# GSM_Power_Source.net
KiCad netlist of a schematic drawn in Altium Designer
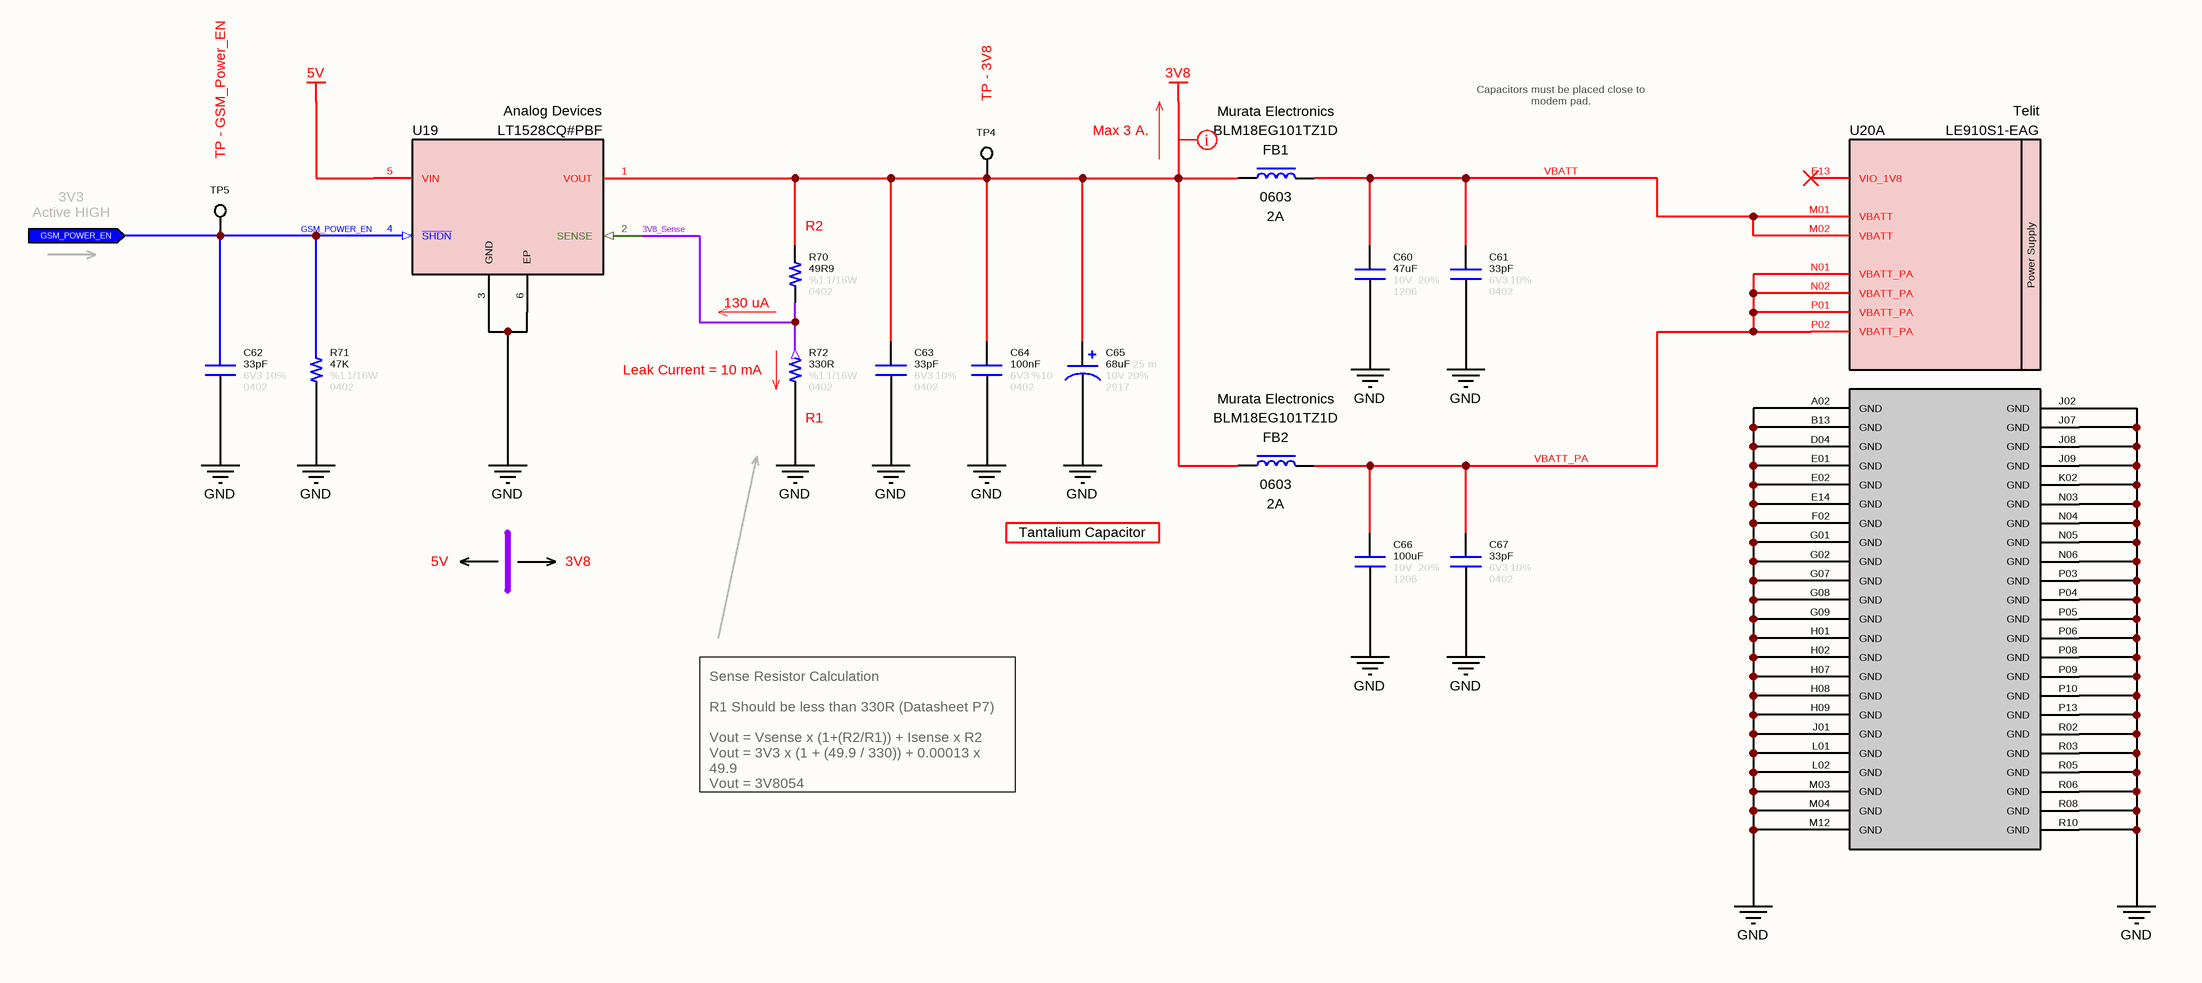
[diagram p0: GSM Power Source.SchDoc]

(export (version "E")
  (design (tool "Eeschema 10.0.6"))
  (components
    (comp (ref "C60")
      (value "47uF")
      (footprint "CAPACITOR_1206")
      (description "Multilayer Ceramic Capacitors MLCC - SMD/SMT 47UF 10V 20% 1206")
      (fields
        (field (name "MANUFACTURER PART NUMBER") "C1206C476M8PAC")
        (field (name "TOLERANCE") "20%")
        (field (name "CASE") "1206")
        (field (name "VOLTAGE") "10V")
        (field (name "Comment") "Capacitor - 47uF [1206] (Ceramic)")
      )
      (libsource (lib "Akkoyun") (part "Capacitor - 47uF [1206-10V]"))
    )
    (comp (ref "C61")
      (value "33pF")
      (footprint "CAPACITOR_0402")
      (description "Capacitor - 33pF [0402] (Ceramic)")
      (fields
        (field (name "MANUFACTURER PART NUMBER") "C0402C330J9RACAUTO")
        (field (name "TOLERANCE") "10%")
        (field (name "CASE") "0402")
        (field (name "VOLTAGE") "6V3")
      )
      (libsource (lib "Akkoyun") (part "Capacitor - 33pF [0402-6V3]"))
    )
    (comp (ref "C62")
      (value "33pF")
      (footprint "CAPACITOR_0402")
      (description "Capacitor - 33pF [0402] (Ceramic)")
      (fields
        (field (name "MANUFACTURER PART NUMBER") "C0402C330J9RACAUTO")
        (field (name "TOLERANCE") "10%")
        (field (name "CASE") "0402")
        (field (name "VOLTAGE") "6V3")
      )
      (libsource (lib "Akkoyun") (part "Capacitor - 33pF [0402-6V3]"))
    )
    (comp (ref "C63")
      (value "33pF")
      (footprint "CAPACITOR_0402")
      (description "Capacitor - 33pF [0402] (Ceramic)")
      (fields
        (field (name "MANUFACTURER PART NUMBER") "C0402C330J9RACAUTO")
        (field (name "TOLERANCE") "10%")
        (field (name "CASE") "0402")
        (field (name "VOLTAGE") "6V3")
      )
      (libsource (lib "Akkoyun") (part "Capacitor - 33pF [0402-6V3]"))
    )
    (comp (ref "C64")
      (value "100nF")
      (footprint "CAPACITOR_0402")
      (description "Capacitor - 100nF [0402-6V3] (Ceramic)")
      (fields
        (field (name "MANUFACTURER PART NUMBER") "04026D104KAT4A")
        (field (name "TOLERANCE") "%10")
        (field (name "VOLTAGE") "6V3")
        (field (name "CASE") "0402")
        (field (name "Comment") "Capacitor - 100nF [0402] (Ceramic)")
      )
      (libsource (lib "Akkoyun") (part "Capacitor - 100nF [0402-6V3]"))
    )
    (comp (ref "C65")
      (value "68uF")
      (footprint "CAP_10TPE68M")
      (description "Tantalum Capacitors - Polymer 10V 68uF 2917 20% ESR=25mOhms")
      (fields
        (field (name "MANUFACTURER PART NUMBER") "10TPE68M")
        (field (name "ESR") "25 m")
        (field (name "TOLERANCE") "20%")
        (field (name "CASE") "2917")
        (field (name "VOLTAGE") "10V")
        (field (name "Comment") "Capacitor - 68uF [2917] (Tantalum)")
      )
      (libsource (lib "Akkoyun") (part "Capacitor - 68uF [2917-10V] (Tantalium)"))
    )
    (comp (ref "C66")
      (value "100uF")
      (footprint "CAPACITOR_1206")
      (description "Multilayer Ceramic Capacitors MLCC - SMD/SMT 100UF 10V 20% 1206")
      (fields
        (field (name "MANUFACTURER PART NUMBER") "GRM31CR61A107MEA8L")
        (field (name "TOLERANCE") "20%")
        (field (name "CASE") "1206")
        (field (name "VOLTAGE") "10V")
        (field (name "Comment") "Capacitor - 100uF [1206] (Ceramic)")
      )
      (libsource (lib "Akkoyun") (part "Capacitor - 100uF [1206-10V]"))
    )
    (comp (ref "C67")
      (value "33pF")
      (footprint "CAPACITOR_0402")
      (description "Capacitor - 33pF [0402] (Ceramic)")
      (fields
        (field (name "MANUFACTURER PART NUMBER") "C0402C330J9RACAUTO")
        (field (name "TOLERANCE") "10%")
        (field (name "CASE") "0402")
        (field (name "VOLTAGE") "6V3")
      )
      (libsource (lib "Akkoyun") (part "Capacitor - 33pF [0402-6V3]"))
    )
    (comp (ref "FB1")
      (value "Ferrite Bead")
      (footprint "INDUCTOR_0603")
      (description "Ferrite Beads 0603 100ohms 2000mA Auto Infotainment")
      (fields
        (field (name "TOLERANCE") "25%")
        (field (name "MAXIMUM DC CURRENT") "2A")
        (field (name "CASE") "0603")
        (field (name "MANUFACTURER PART NUMBER") "BLM18EG101TZ1D")
        (field (name "MANUFACTURER NAME") "Murata Electronics")
      )
      (libsource (lib "Akkoyun") (part "Inductor - Ferrite Bead [SMD]"))
    )
    (comp (ref "FB2")
      (value "Ferrite Bead")
      (footprint "INDUCTOR_0603")
      (description "Ferrite Beads 0603 100ohms 2000mA Auto Infotainment")
      (fields
        (field (name "TOLERANCE") "25%")
        (field (name "MAXIMUM DC CURRENT") "2A")
        (field (name "CASE") "0603")
        (field (name "MANUFACTURER PART NUMBER") "BLM18EG101TZ1D")
        (field (name "MANUFACTURER NAME") "Murata Electronics")
      )
      (libsource (lib "Akkoyun") (part "Inductor - Ferrite Bead [SMD]"))
    )
    (comp (ref "R70")
      (value "49R9")
      (footprint "RESISTOR_0402")
      (description "Thick Film Resistors - SMD 1/16 W 49.9 Ohm 1%")
      (fields
        (field (name "MANUFACTURER PART NUMBER") "CRCW040249R9FKED")
        (field (name "CASE") "0402")
        (field (name "TOLERANCE") "%1")
        (field (name "POWER") "1/16W")
        (field (name "Comment") "49R9 - 0402 - %1 - 1/16W")
      )
      (libsource (lib "Akkoyun") (part "Resistor - 49R9 [0402]"))
    )
    (comp (ref "R71")
      (value "47K")
      (footprint "RESISTOR_0402")
      (description "Thick Film Resistors - SMD 1/16 W 47 KOhm 1%")
      (fields
        (field (name "MANUFACTURER PART NUMBER") "CRCW040247K0FKED")
        (field (name "TOLERANCE") "%1")
        (field (name "CASE") "0402")
        (field (name "POWER") "1/16W")
        (field (name "Comment") "47K - 0402 - %1 - 1/16W")
      )
      (libsource (lib "Akkoyun") (part "Resistor - 47K [0402]"))
    )
    (comp (ref "R72")
      (value "330R")
      (footprint "RESISTOR_0402")
      (description "Thick Film Resistors - SMD 1/16 W 330 Ohm 1%")
      (fields
        (field (name "MANUFACTURER PART NUMBER") "CRCW0402330RFKED")
        (field (name "CASE") "0402")
        (field (name "TOLERANCE") "%1")
        (field (name "POWER") "1/16W")
        (field (name "Comment") "330R - 0402 - %1 - 1/16W")
      )
      (libsource (lib "Akkoyun") (part "Resistor - 330R [0402]"))
    )
    (comp (ref "TP4")
      (value "TP - 3V8")
      (footprint "TP")
      (description "Test Point")
      (libsource (lib "Akkoyun") (part "PCB - Test Point"))
    )
    (comp (ref "TP5")
      (value "TP - GSM_Power_EN")
      (footprint "TP")
      (description "Test Point")
      (libsource (lib "Akkoyun") (part "PCB - Test Point"))
    )
    (comp (ref "U19")
      (value "LDO Regulator")
      (footprint "DDPAK-5")
      (description "LDO Voltage Regulators 3A L Drop Reg for uP Applications")
      (fields
        (field (name "MANUFACTURER PART NUMBER") "LT1528CQ#PBF")
        (field (name "MANUFACTURER NAME") "Analog Devices")
      )
      (libsource (lib "Akkoyun") (part "IC - LT1528CQ"))
    )
    (comp (ref "U20")
      (value "LE910S1-EAG LTE GSM Module")
      (footprint "LE910 GSM Modem")
      (description "Telit LE910S1-EAG GPRS/GNSS Module")
      (fields
        (field (name "MANUFACTURER PART NUMBER") "LE910S1-EAG")
        (field (name "MANUFACTURER NAME") "Telit")
      )
      (libsource (lib "Akkoyun") (part "IC - LE910S1-EAG"))
    )
  )
  (nets
    (net (code "1") (name "/3V8_Sense") (class "Default")
      (node (ref "R70") (pin "1") (pinfunction "1_1") (pintype "passive"))
      (node (ref "R72") (pin "2") (pinfunction "2_2") (pintype "output"))
      (node (ref "U19") (pin "2") (pinfunction "SENSE_2") (pintype "input"))
    )
    (net (code "2") (name "/GSM_POWER_EN") (class "Default")
      (node (ref "C62") (pin "2") (pinfunction "2_2") (pintype "passive"))
      (node (ref "R71") (pin "2") (pinfunction "2_2") (pintype "passive"))
      (node (ref "TP5") (pin "1") (pinfunction "1_1") (pintype "passive"))
      (node (ref "U19") (pin "4") (pinfunction "~{SHDN}_4") (pintype "input"))
    )
    (net (code "3") (name "/VBATT") (class "Default")
      (node (ref "C60") (pin "2") (pinfunction "2_2") (pintype "passive"))
      (node (ref "C61") (pin "2") (pinfunction "2_2") (pintype "passive"))
      (node (ref "FB1") (pin "2") (pinfunction "2_2") (pintype "passive"))
      (node (ref "U20") (pin "M01") (pinfunction "VBATT_M01") (pintype "power_in"))
      (node (ref "U20") (pin "M02") (pinfunction "VBATT_M02") (pintype "power_in"))
    )
    (net (code "4") (name "/VBATT_PA") (class "Default")
      (node (ref "C66") (pin "2") (pinfunction "2_2") (pintype "passive"))
      (node (ref "C67") (pin "2") (pinfunction "2_2") (pintype "passive"))
      (node (ref "FB2") (pin "2") (pinfunction "2_2") (pintype "passive"))
      (node (ref "U20") (pin "N01") (pinfunction "VBATT_PA_N01") (pintype "power_in"))
      (node (ref "U20") (pin "N02") (pinfunction "VBATT_PA_N02") (pintype "power_in"))
      (node (ref "U20") (pin "P01") (pinfunction "VBATT_PA_P01") (pintype "power_in"))
      (node (ref "U20") (pin "P02") (pinfunction "VBATT_PA_P02") (pintype "power_in"))
    )
    (net (code "5") (name "3V8") (class "Default")
      (node (ref "C63") (pin "2") (pinfunction "2_2") (pintype "passive"))
      (node (ref "C64") (pin "2") (pinfunction "2_2") (pintype "passive"))
      (node (ref "C65") (pin "1") (pinfunction "1_1") (pintype "passive"))
      (node (ref "FB1") (pin "1") (pinfunction "1_1") (pintype "passive"))
      (node (ref "FB2") (pin "1") (pinfunction "1_1") (pintype "passive"))
      (node (ref "R70") (pin "2") (pinfunction "2_2") (pintype "passive"))
      (node (ref "TP4") (pin "1") (pinfunction "1_1") (pintype "passive"))
      (node (ref "U19") (pin "1") (pinfunction "VOUT_1") (pintype "power_in"))
    )
    (net (code "6") (name "5V") (class "Default")
      (node (ref "U19") (pin "5") (pinfunction "VIN_5") (pintype "power_in"))
    )
    (net (code "7") (name "GND") (class "Default")
      (node (ref "C60") (pin "1") (pinfunction "1_1") (pintype "passive"))
      (node (ref "C61") (pin "1") (pinfunction "1_1") (pintype "passive"))
      (node (ref "C62") (pin "1") (pinfunction "1_1") (pintype "passive"))
      (node (ref "C63") (pin "1") (pinfunction "1_1") (pintype "passive"))
      (node (ref "C64") (pin "1") (pinfunction "1_1") (pintype "passive"))
      (node (ref "C65") (pin "2") (pinfunction "2_2") (pintype "passive"))
      (node (ref "C66") (pin "1") (pinfunction "1_1") (pintype "passive"))
      (node (ref "C67") (pin "1") (pinfunction "1_1") (pintype "passive"))
      (node (ref "R71") (pin "1") (pinfunction "1_1") (pintype "passive"))
      (node (ref "R72") (pin "1") (pinfunction "1_1") (pintype "passive"))
      (node (ref "U19") (pin "3") (pinfunction "GND_3") (pintype "power_in"))
      (node (ref "U19") (pin "6") (pinfunction "EP_6") (pintype "power_in"))
      (node (ref "U20") (pin "A02") (pinfunction "GND_A02") (pintype "power_in"))
      (node (ref "U20") (pin "B13") (pinfunction "GND_B13") (pintype "power_in"))
      (node (ref "U20") (pin "D04") (pinfunction "GND_D04") (pintype "power_in"))
      (node (ref "U20") (pin "E01") (pinfunction "GND_E01") (pintype "power_in"))
      (node (ref "U20") (pin "E02") (pinfunction "GND_E02") (pintype "power_in"))
      (node (ref "U20") (pin "E14") (pinfunction "GND_E14") (pintype "power_in"))
      (node (ref "U20") (pin "F02") (pinfunction "GND_F02") (pintype "power_in"))
      (node (ref "U20") (pin "G01") (pinfunction "GND_G01") (pintype "power_in"))
      (node (ref "U20") (pin "G02") (pinfunction "GND_G02") (pintype "power_in"))
      (node (ref "U20") (pin "G07") (pinfunction "GND_G07") (pintype "power_in"))
      (node (ref "U20") (pin "G08") (pinfunction "GND_G08") (pintype "power_in"))
      (node (ref "U20") (pin "G09") (pinfunction "GND_G09") (pintype "power_in"))
      (node (ref "U20") (pin "H01") (pinfunction "GND_H01") (pintype "power_in"))
      (node (ref "U20") (pin "H02") (pinfunction "GND_H02") (pintype "power_in"))
      (node (ref "U20") (pin "H07") (pinfunction "GND_H07") (pintype "power_in"))
      (node (ref "U20") (pin "H08") (pinfunction "GND_H08") (pintype "power_in"))
      (node (ref "U20") (pin "H09") (pinfunction "GND_H09") (pintype "power_in"))
      (node (ref "U20") (pin "J01") (pinfunction "GND_J01") (pintype "power_in"))
      (node (ref "U20") (pin "J02") (pinfunction "GND_J02") (pintype "power_in"))
      (node (ref "U20") (pin "J07") (pinfunction "GND_J07") (pintype "power_in"))
      (node (ref "U20") (pin "J08") (pinfunction "GND_J08") (pintype "power_in"))
      (node (ref "U20") (pin "J09") (pinfunction "GND_J09") (pintype "power_in"))
      (node (ref "U20") (pin "K02") (pinfunction "GND_K02") (pintype "power_in"))
      (node (ref "U20") (pin "L01") (pinfunction "GND_L01") (pintype "power_in"))
      (node (ref "U20") (pin "L02") (pinfunction "GND_L02") (pintype "power_in"))
      (node (ref "U20") (pin "M03") (pinfunction "GND_M03") (pintype "power_in"))
      (node (ref "U20") (pin "M04") (pinfunction "GND_M04") (pintype "power_in"))
      (node (ref "U20") (pin "M12") (pinfunction "GND_M12") (pintype "power_in"))
      (node (ref "U20") (pin "N03") (pinfunction "GND_N03") (pintype "power_in"))
      (node (ref "U20") (pin "N04") (pinfunction "GND_N04") (pintype "power_in"))
      (node (ref "U20") (pin "N05") (pinfunction "GND_N05") (pintype "power_in"))
      (node (ref "U20") (pin "N06") (pinfunction "GND_N06") (pintype "power_in"))
      (node (ref "U20") (pin "P03") (pinfunction "GND_P03") (pintype "power_in"))
      (node (ref "U20") (pin "P04") (pinfunction "GND_P04") (pintype "power_in"))
      (node (ref "U20") (pin "P05") (pinfunction "GND_P05") (pintype "power_in"))
      (node (ref "U20") (pin "P06") (pinfunction "GND_P06") (pintype "power_in"))
      (node (ref "U20") (pin "P08") (pinfunction "GND_P08") (pintype "power_in"))
      (node (ref "U20") (pin "P09") (pinfunction "GND_P09") (pintype "power_in"))
      (node (ref "U20") (pin "P10") (pinfunction "GND_P10") (pintype "power_in"))
      (node (ref "U20") (pin "P13") (pinfunction "GND_P13") (pintype "power_in"))
      (node (ref "U20") (pin "R02") (pinfunction "GND_R02") (pintype "power_in"))
      (node (ref "U20") (pin "R03") (pinfunction "GND_R03") (pintype "power_in"))
      (node (ref "U20") (pin "R05") (pinfunction "GND_R05") (pintype "power_in"))
      (node (ref "U20") (pin "R06") (pinfunction "GND_R06") (pintype "power_in"))
      (node (ref "U20") (pin "R08") (pinfunction "GND_R08") (pintype "power_in"))
      (node (ref "U20") (pin "R10") (pinfunction "GND_R10") (pintype "power_in"))
    )
    (net (code "8") (name "unconnected-(U20A-VIO_1V8-PadE13)") (class "Default")
      (node (ref "U20") (pin "E13") (pinfunction "VIO_1V8_E13") (pintype "power_in+no_connect"))
    )
  )
)
